# ADNS-9800.net
KiCad netlist of a schematic drawn in EAGLE
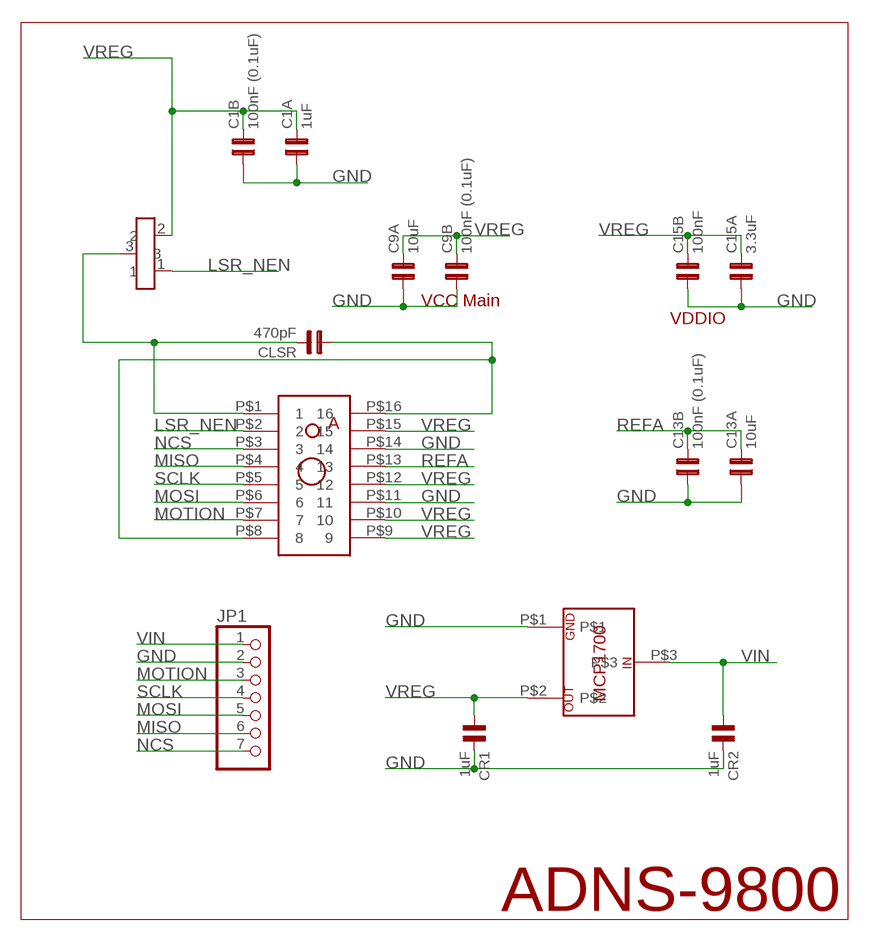
[diagram p0: schematic, sheet 1]

(export (version "E")
  (design (tool "Eeschema 10.0.6"))
  (components
    (comp (ref "C1A")
      (value "1uF")
      (footprint "eagle-import:0603")
      (libsource (lib "eagle-import") (part "C0603"))
    )
    (comp (ref "C1B")
      (value "100nF (0.1uF)")
      (footprint "eagle-import:0603")
      (libsource (lib "eagle-import") (part "C0603"))
    )
    (comp (ref "C9A")
      (value "10uF")
      (footprint "eagle-import:0603")
      (libsource (lib "eagle-import") (part "C0603"))
    )
    (comp (ref "C9B")
      (value "100nF (0.1uF)")
      (footprint "eagle-import:0603")
      (libsource (lib "eagle-import") (part "C0603"))
    )
    (comp (ref "C13A")
      (value "10uF")
      (footprint "eagle-import:0603")
      (libsource (lib "eagle-import") (part "C0603"))
    )
    (comp (ref "C13B")
      (value "100nF (0.1uF)")
      (footprint "eagle-import:0603")
      (libsource (lib "eagle-import") (part "C0603"))
    )
    (comp (ref "C15A")
      (value "3.3uF")
      (footprint "eagle-import:0603")
      (libsource (lib "eagle-import") (part "C0603"))
    )
    (comp (ref "C15B")
      (value "100nF")
      (footprint "eagle-import:0603")
      (libsource (lib "eagle-import") (part "C0603"))
    )
    (comp (ref "CLSR")
      (value "470pF")
      (footprint "eagle-import:0603")
      (libsource (lib "eagle-import") (part "C0603"))
    )
    (comp (ref "CR1")
      (value "1uF")
      (footprint "eagle-import:0603")
      (libsource (lib "eagle-import") (part "C0603"))
    )
    (comp (ref "CR2")
      (value "1uF")
      (footprint "eagle-import:0603")
      (libsource (lib "eagle-import") (part "C0603"))
    )
    (comp (ref "JP1")
      (value "PINHD-1X7")
      (footprint "eagle-import:1X07")
      (libsource (lib "eagle-import") (part "PINHD-1X7"))
    )
    (comp (ref "Q1")
      (value "TRANSISTOR_SC-75")
      (footprint "eagle-import:SC-75_TRANSISTOR")
      (libsource (lib "eagle-import") (part "TRANSISTOR_SC-75"))
    )
    (comp (ref "U$1")
      (value "AVAGO_ADNS-9500")
      (footprint "eagle-import:AVAGO_ADNS-9500")
      (libsource (lib "eagle-import") (part "AVAGO_ADNS-9500"))
    )
    (comp (ref "U$2")
      (value "MCP1700__LDO")
      (footprint "eagle-import:MCP1700__LDO")
      (libsource (lib "eagle-import") (part "MCP1700__LDO"))
    )
  )
  (nets
    (net (code "1") (name "/GND") (class "Default")
      (node (ref "C13A") (pin "1") (pinfunction "1_1") (pintype "passive"))
      (node (ref "C13B") (pin "1") (pinfunction "1_1") (pintype "passive"))
      (node (ref "C15A") (pin "1") (pinfunction "1_1") (pintype "passive"))
      (node (ref "C15B") (pin "1") (pinfunction "1_1") (pintype "passive"))
      (node (ref "C1A") (pin "1") (pinfunction "1_1") (pintype "passive"))
      (node (ref "C1B") (pin "1") (pinfunction "1_1") (pintype "passive"))
      (node (ref "C9A") (pin "1") (pinfunction "1_1") (pintype "passive"))
      (node (ref "C9B") (pin "1") (pinfunction "1_1") (pintype "passive"))
      (node (ref "CR1") (pin "2") (pinfunction "2_2") (pintype "passive"))
      (node (ref "CR2") (pin "2") (pinfunction "2_2") (pintype "passive"))
      (node (ref "JP1") (pin "2") (pinfunction "2_2") (pintype "passive"))
      (node (ref "U$1") (pin "P$11") (pinfunction "11_P$11") (pintype "bidirectional"))
      (node (ref "U$1") (pin "P$14") (pinfunction "14_P$14") (pintype "bidirectional"))
      (node (ref "U$2") (pin "P$1") (pinfunction "P$1_P$1") (pintype "bidirectional"))
    )
    (net (code "2") (name "/LSR_NEN") (class "Default")
      (node (ref "Q1") (pin "1") (pinfunction "1_1") (pintype "bidirectional"))
      (node (ref "U$1") (pin "P$2") (pinfunction "2_P$2") (pintype "bidirectional"))
    )
    (net (code "3") (name "/MISO") (class "Default")
      (node (ref "JP1") (pin "6") (pinfunction "6_6") (pintype "passive"))
      (node (ref "U$1") (pin "P$4") (pinfunction "4_P$4") (pintype "bidirectional"))
    )
    (net (code "4") (name "/MOSI") (class "Default")
      (node (ref "JP1") (pin "5") (pinfunction "5_5") (pintype "passive"))
      (node (ref "U$1") (pin "P$6") (pinfunction "6_P$6") (pintype "bidirectional"))
    )
    (net (code "5") (name "/MOTION") (class "Default")
      (node (ref "JP1") (pin "3") (pinfunction "3_3") (pintype "passive"))
      (node (ref "U$1") (pin "P$7") (pinfunction "7_P$7") (pintype "bidirectional"))
    )
    (net (code "6") (name "/NCS") (class "Default")
      (node (ref "JP1") (pin "7") (pinfunction "7_7") (pintype "passive"))
      (node (ref "U$1") (pin "P$3") (pinfunction "3_P$3") (pintype "bidirectional"))
    )
    (net (code "7") (name "/REFA") (class "Default")
      (node (ref "C13A") (pin "2") (pinfunction "2_2") (pintype "passive"))
      (node (ref "C13B") (pin "2") (pinfunction "2_2") (pintype "passive"))
      (node (ref "U$1") (pin "P$13") (pinfunction "13_P$13") (pintype "bidirectional"))
    )
    (net (code "8") (name "/SCLK") (class "Default")
      (node (ref "JP1") (pin "4") (pinfunction "4_4") (pintype "passive"))
      (node (ref "U$1") (pin "P$5") (pinfunction "5_P$5") (pintype "bidirectional"))
    )
    (net (code "9") (name "/VIN") (class "Default")
      (node (ref "CR2") (pin "1") (pinfunction "1_1") (pintype "passive"))
      (node (ref "JP1") (pin "1") (pinfunction "1_1") (pintype "passive"))
      (node (ref "U$2") (pin "P$3") (pinfunction "P$3_P$3") (pintype "bidirectional"))
    )
    (net (code "10") (name "/VREG") (class "Default")
      (node (ref "C15A") (pin "2") (pinfunction "2_2") (pintype "passive"))
      (node (ref "C15B") (pin "2") (pinfunction "2_2") (pintype "passive"))
      (node (ref "C1A") (pin "2") (pinfunction "2_2") (pintype "passive"))
      (node (ref "C1B") (pin "2") (pinfunction "2_2") (pintype "passive"))
      (node (ref "C9A") (pin "2") (pinfunction "2_2") (pintype "passive"))
      (node (ref "C9B") (pin "2") (pinfunction "2_2") (pintype "passive"))
      (node (ref "CR1") (pin "1") (pinfunction "1_1") (pintype "passive"))
      (node (ref "Q1") (pin "2") (pinfunction "2_2") (pintype "bidirectional"))
      (node (ref "U$1") (pin "P$10") (pinfunction "10_P$10") (pintype "bidirectional"))
      (node (ref "U$1") (pin "P$12") (pinfunction "12_P$12") (pintype "bidirectional"))
      (node (ref "U$1") (pin "P$15") (pinfunction "15_P$15") (pintype "bidirectional"))
      (node (ref "U$1") (pin "P$9") (pinfunction "9_P$9") (pintype "bidirectional"))
      (node (ref "U$2") (pin "P$2") (pinfunction "P$2_P$2") (pintype "bidirectional"))
    )
    (net (code "11") (name "Net-(U$1-1)") (class "Default")
      (node (ref "CLSR") (pin "2") (pinfunction "2_2") (pintype "passive"))
      (node (ref "Q1") (pin "3") (pinfunction "3_3") (pintype "bidirectional"))
      (node (ref "U$1") (pin "P$1") (pinfunction "1_P$1") (pintype "bidirectional"))
    )
    (net (code "12") (name "Net-(U$1-16)") (class "Default")
      (node (ref "CLSR") (pin "1") (pinfunction "1_1") (pintype "passive"))
      (node (ref "U$1") (pin "P$16") (pinfunction "16_P$16") (pintype "bidirectional"))
      (node (ref "U$1") (pin "P$8") (pinfunction "8_P$8") (pintype "bidirectional"))
    )
  )
)
